# Power_Supply.net
KiCad netlist of a schematic drawn in Altium Designer
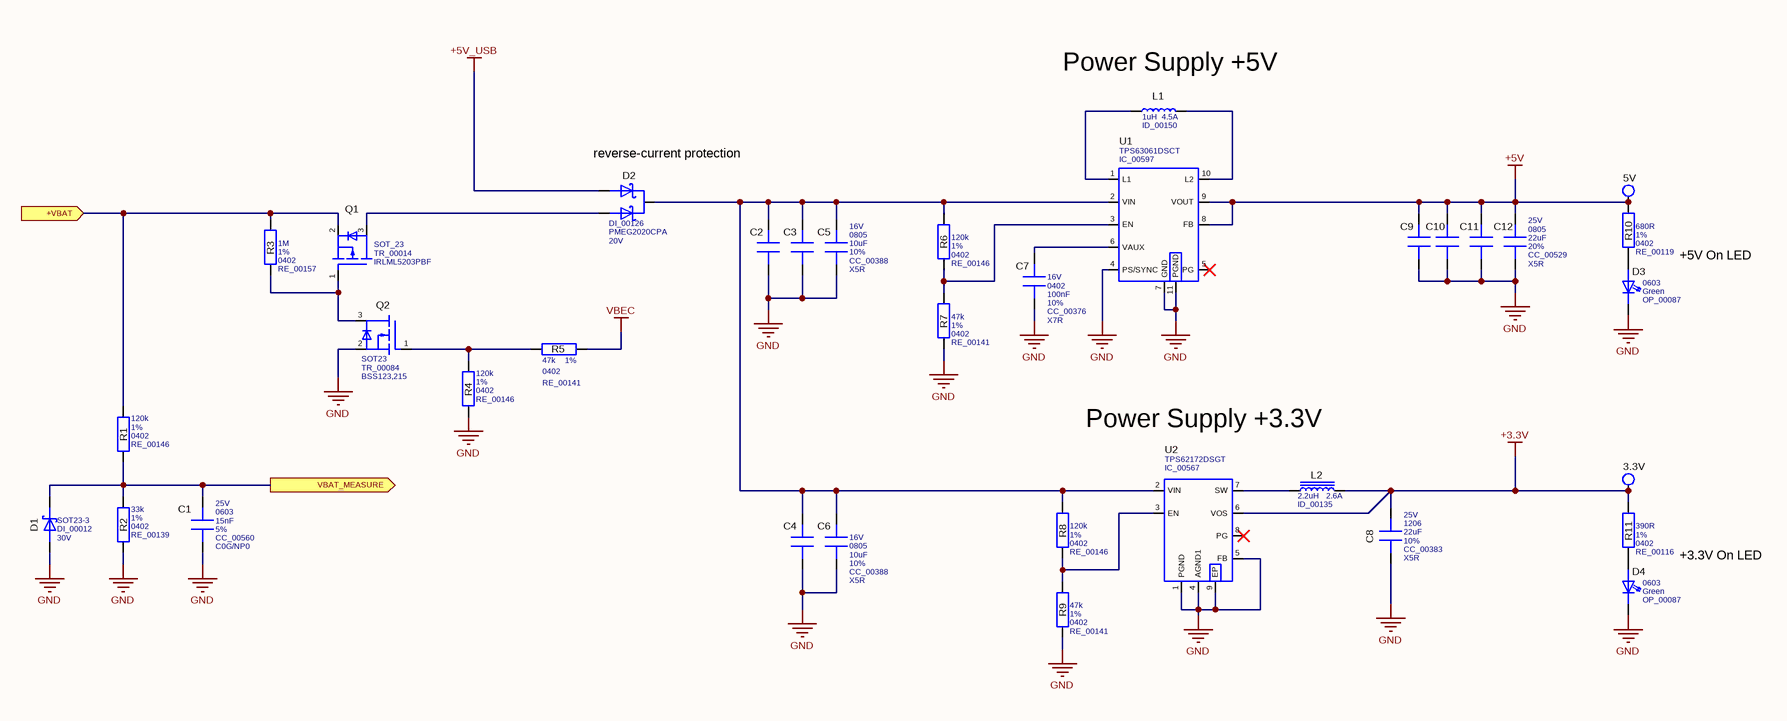
[diagram p0: Power Supply.SchDoc]

(export (version "E")
  (design (tool "Eeschema 10.0.6"))
  (components
    (comp (ref "3.3V")
      (value "testpoint")
      (footprint "CO_00057N")
      (description "Testpoint 1.6mm Bohrung 1mm")
      (fields
        (field (name "PART_NUMBER") "CO_00057")
        (field (name "POWER") "0W")
        (field (name "CREATOR") "Sirnik Heimo")
      )
      (libsource (lib "Central Library") (part "testpoint"))
    )
    (comp (ref "5V")
      (value "testpoint")
      (footprint "CO_00057N")
      (description "Testpoint 1.6mm Bohrung 1mm")
      (fields
        (field (name "PART_NUMBER") "CO_00057")
        (field (name "POWER") "0W")
        (field (name "CREATOR") "Sirnik Heimo")
      )
      (libsource (lib "Central Library") (part "testpoint"))
    )
    (comp (ref "C1")
      (value "capacitor")
      (footprint "CS1600X800X900X350X1250L")
      (fields
        (field (name "VOLTAGE") "25V")
        (field (name "PACKAGE") "0603")
        (field (name "CAPACITANCE") "15nF")
        (field (name "TOLERANCE") "5%")
        (field (name "PART_NUMBER") "CC_00560")
        (field (name "DIELECTRIC_MATERIAL") "C0G/NP0")
        (field (name "CREATOR") "Krenn Markus")
      )
      (libsource (lib "Central Library") (part "capacitor"))
    )
    (comp (ref "C2")
      (value "capacitor")
      (footprint "CS2000x1250x1250x350x1650L")
      (fields
        (field (name "VOLTAGE") "16V")
        (field (name "TOLERANCE") "10%")
        (field (name "PART_NUMBER") "CC_00388")
        (field (name "CREATOR") "Krenn Markus")
      )
      (libsource (lib "Central Library") (part "capacitor"))
    )
    (comp (ref "C3")
      (value "capacitor")
      (footprint "CS2000x1250x1250x350x1650L")
      (fields
        (field (name "VOLTAGE") "16V")
        (field (name "TOLERANCE") "10%")
        (field (name "PART_NUMBER") "CC_00388")
        (field (name "CREATOR") "Krenn Markus")
      )
      (libsource (lib "Central Library") (part "capacitor"))
    )
    (comp (ref "C4")
      (value "capacitor")
      (footprint "CS2000x1250x1250x350x1650L")
      (fields
        (field (name "VOLTAGE") "16V")
        (field (name "TOLERANCE") "10%")
        (field (name "PART_NUMBER") "CC_00388")
        (field (name "CREATOR") "Krenn Markus")
      )
      (libsource (lib "Central Library") (part "capacitor"))
    )
    (comp (ref "C5")
      (value "capacitor")
      (footprint "CS2000x1250x1250x350x1650L")
      (fields
        (field (name "VOLTAGE") "16V")
        (field (name "PACKAGE") "0805")
        (field (name "CAPACITANCE") "10uF")
        (field (name "TOLERANCE") "10%")
        (field (name "PART_NUMBER") "CC_00388")
        (field (name "DIELECTRIC_MATERIAL") "X5R")
        (field (name "CREATOR") "Krenn Markus")
      )
      (libsource (lib "Central Library") (part "capacitor"))
    )
    (comp (ref "C6")
      (value "capacitor")
      (footprint "CS2000x1250x1250x350x1650L")
      (fields
        (field (name "VOLTAGE") "16V")
        (field (name "PACKAGE") "0805")
        (field (name "CAPACITANCE") "10uF")
        (field (name "TOLERANCE") "10%")
        (field (name "PART_NUMBER") "CC_00388")
        (field (name "DIELECTRIC_MATERIAL") "X5R")
        (field (name "CREATOR") "Krenn Markus")
      )
      (libsource (lib "Central Library") (part "capacitor"))
    )
    (comp (ref "C7")
      (value "capacitor")
      (footprint "CS1000X500X560X250X820L")
      (fields
        (field (name "VOLTAGE") "16V")
        (field (name "PACKAGE") "0402")
        (field (name "CAPACITANCE") "100nF")
        (field (name "TOLERANCE") "10%")
        (field (name "PART_NUMBER") "CC_00376")
        (field (name "DIELECTRIC_MATERIAL") "X7R")
        (field (name "CREATOR") "Okorn Robert")
      )
      (libsource (lib "Central Library") (part "capacitor"))
    )
    (comp (ref "C8")
      (value "capacitor")
      (footprint "CS3200x1600x900x500x2700L")
      (fields
        (field (name "VOLTAGE") "25V")
        (field (name "PACKAGE") "1206")
        (field (name "CAPACITANCE") "22uF")
        (field (name "TOLERANCE") "10%")
        (field (name "PART_NUMBER") "CC_00383")
        (field (name "DIELECTRIC_MATERIAL") "X5R")
        (field (name "CREATOR") "Neissl Gernot")
      )
      (libsource (lib "Central Library") (part "capacitor"))
    )
    (comp (ref "C9")
      (value "capacitor")
      (footprint "CS2000x1250x1250x350x1650L")
      (fields
        (field (name "VOLTAGE") "25V")
        (field (name "TOLERANCE") "20%")
        (field (name "PART_NUMBER") "CC_00529")
        (field (name "CREATOR") "Neissl Gernot")
      )
      (libsource (lib "Central Library") (part "capacitor"))
    )
    (comp (ref "C10")
      (value "capacitor")
      (footprint "CS2000x1250x1250x350x1650L")
      (fields
        (field (name "VOLTAGE") "25V")
        (field (name "TOLERANCE") "20%")
        (field (name "PART_NUMBER") "CC_00529")
        (field (name "CREATOR") "Neissl Gernot")
      )
      (libsource (lib "Central Library") (part "capacitor"))
    )
    (comp (ref "C11")
      (value "capacitor")
      (footprint "CS2000x1250x1250x350x1650L")
      (fields
        (field (name "VOLTAGE") "25V")
        (field (name "TOLERANCE") "20%")
        (field (name "PART_NUMBER") "CC_00529")
        (field (name "CREATOR") "Neissl Gernot")
      )
      (libsource (lib "Central Library") (part "capacitor"))
    )
    (comp (ref "C12")
      (value "capacitor")
      (footprint "CS2000x1250x1250x350x1650L")
      (fields
        (field (name "VOLTAGE") "25V")
        (field (name "PACKAGE") "0805")
        (field (name "CAPACITANCE") "22uF")
        (field (name "TOLERANCE") "20%")
        (field (name "PART_NUMBER") "CC_00529")
        (field (name "DIELECTRIC_MATERIAL") "X5R")
        (field (name "CREATOR") "Neissl Gernot")
      )
      (libsource (lib "Central Library") (part "capacitor"))
    )
    (comp (ref "D1")
      (value "DI_00012")
      (footprint "DI_00012N")
      (description "BAR43 - Schottky Diode, 30V, 100mA")
      (fields
        (field (name "PACKAGE") "SOT23-3")
        (field (name "POWER") "0W")
        (field (name "PART_NUMBER") "DI_00012")
        (field (name "REVERSE_VOLTAGE") "30V")
        (field (name "CREATOR") "Krenn Markus")
      )
      (libsource (lib "Central Library") (part "DI_00012"))
    )
    (comp (ref "D2")
      (value "DI_00126")
      (footprint "DI_00126N")
      (description "2 A low V F  dual MEGA Schottky barrier rectifier")
      (fields
        (field (name "POWER") "500mW")
        (field (name "PART_NUMBER") "DI_00126")
        (field (name "MANUFACTURER_NUMBER") "PMEG2020CPA")
        (field (name "REVERSE_VOLTAGE") "20V")
        (field (name "CREATOR") "Krenn Markus")
      )
      (libsource (lib "Central Library") (part "DI_00126"))
    )
    (comp (ref "D3")
      (value "LED")
      (footprint "OP_00087L")
      (fields
        (field (name "PACKAGE") "0603")
        (field (name "COLOR") "Green")
        (field (name "PART_NUMBER") "OP_00087")
        (field (name "CREATOR") "Krenn Markus")
      )
      (libsource (lib "Central Library") (part "LED"))
    )
    (comp (ref "D4")
      (value "LED")
      (footprint "OP_00087L")
      (fields
        (field (name "PACKAGE") "0603")
        (field (name "COLOR") "Green")
        (field (name "PART_NUMBER") "OP_00087")
        (field (name "CREATOR") "Krenn Markus")
      )
      (libsource (lib "Central Library") (part "LED"))
    )
    (comp (ref "L1")
      (value "inductor")
      (footprint "ID_00150N")
      (fields
        (field (name "INDUCTANCE") "1uH")
        (field (name "PART_NUMBER") "ID_00150")
        (field (name "CURRENT_DC") "4.5A")
        (field (name "CREATOR") "Krenn Markus")
      )
      (libsource (lib "Central Library") (part "inductor"))
    )
    (comp (ref "L2")
      (value "inductor_shielded")
      (footprint "ID_00135N")
      (fields
        (field (name "INDUCTANCE") "2.2uH")
        (field (name "PART_NUMBER") "ID_00135")
        (field (name "CURRENT_DC") "2.6A")
        (field (name "CREATOR") "Krenn Markus")
      )
      (libsource (lib "Central Library") (part "inductor_shielded"))
    )
    (comp (ref "Q1")
      (value "pmosfet")
      (footprint "TR_00014N")
      (fields
        (field (name "PACKAGE") "SOT_23")
        (field (name "PART_NUMBER") "TR_00014")
        (field (name "MANUFACTURER_NUMBER") "IRLML5203PBF")
        (field (name "CREATOR") "Neissl Gernot")
      )
      (libsource (lib "Central Library") (part "pmosfet"))
    )
    (comp (ref "Q2")
      (value "nmosfet")
      (footprint "TR_00084N")
      (fields
        (field (name "PACKAGE") "SOT23")
        (field (name "PART_NUMBER") "TR_00084")
        (field (name "MANUFACTURER_NUMBER") "BSS123,215")
        (field (name "CREATOR") "Weis Gerald")
      )
      (libsource (lib "Central Library") (part "nmosfet"))
    )
    (comp (ref "R1")
      (value "Resistor")
      (footprint "RS1000X500X560X250X820L")
      (fields
        (field (name "RESISTANCE") "120k")
        (field (name "TOLERANCE") "1%")
        (field (name "PACKAGE") "0402")
        (field (name "PART_NUMBER") "RE_00146")
        (field (name "CREATOR") "Krenn Markus")
      )
      (libsource (lib "Central Library") (part "Resistor"))
    )
    (comp (ref "R2")
      (value "Resistor")
      (footprint "RS1000X500X560X250X820L")
      (fields
        (field (name "RESISTANCE") "33k")
        (field (name "TOLERANCE") "1%")
        (field (name "PACKAGE") "0402")
        (field (name "PART_NUMBER") "RE_00139")
        (field (name "CREATOR") "Krenn Markus")
      )
      (libsource (lib "Central Library") (part "Resistor"))
    )
    (comp (ref "R3")
      (value "Resistor")
      (footprint "RS1000X500X560X250X820L")
      (fields
        (field (name "RESISTANCE") "1M")
        (field (name "TOLERANCE") "1%")
        (field (name "PACKAGE") "0402")
        (field (name "PART_NUMBER") "RE_00157")
        (field (name "CREATOR") "Krenn Markus")
      )
      (libsource (lib "Central Library") (part "Resistor"))
    )
    (comp (ref "R4")
      (value "Resistor")
      (footprint "RS1000X500X560X250X820L")
      (fields
        (field (name "RESISTANCE") "120k")
        (field (name "TOLERANCE") "1%")
        (field (name "PACKAGE") "0402")
        (field (name "PART_NUMBER") "RE_00146")
        (field (name "CREATOR") "Krenn Markus")
      )
      (libsource (lib "Central Library") (part "Resistor"))
    )
    (comp (ref "R5")
      (value "Resistor")
      (footprint "RS1000X500X560X250X820L")
      (fields
        (field (name "RESISTANCE") "47k")
        (field (name "TOLERANCE") "1%")
        (field (name "PACKAGE") "0402")
        (field (name "PART_NUMBER") "RE_00141")
        (field (name "CREATOR") "Krenn Markus")
      )
      (libsource (lib "Central Library") (part "Resistor"))
    )
    (comp (ref "R6")
      (value "Resistor")
      (footprint "RS1000X500X560X250X820L")
      (fields
        (field (name "RESISTANCE") "120k")
        (field (name "TOLERANCE") "1%")
        (field (name "PACKAGE") "0402")
        (field (name "PART_NUMBER") "RE_00146")
        (field (name "CREATOR") "Krenn Markus")
      )
      (libsource (lib "Central Library") (part "Resistor"))
    )
    (comp (ref "R7")
      (value "Resistor")
      (footprint "RS1000X500X560X250X820L")
      (fields
        (field (name "RESISTANCE") "47k")
        (field (name "TOLERANCE") "1%")
        (field (name "PACKAGE") "0402")
        (field (name "PART_NUMBER") "RE_00141")
        (field (name "CREATOR") "Krenn Markus")
      )
      (libsource (lib "Central Library") (part "Resistor"))
    )
    (comp (ref "R8")
      (value "Resistor")
      (footprint "RS1000X500X560X250X820L")
      (fields
        (field (name "RESISTANCE") "120k")
        (field (name "TOLERANCE") "1%")
        (field (name "PACKAGE") "0402")
        (field (name "PART_NUMBER") "RE_00146")
        (field (name "CREATOR") "Krenn Markus")
      )
      (libsource (lib "Central Library") (part "Resistor"))
    )
    (comp (ref "R9")
      (value "Resistor")
      (footprint "RS1000X500X560X250X820L")
      (fields
        (field (name "RESISTANCE") "47k")
        (field (name "TOLERANCE") "1%")
        (field (name "PACKAGE") "0402")
        (field (name "PART_NUMBER") "RE_00141")
        (field (name "CREATOR") "Krenn Markus")
      )
      (libsource (lib "Central Library") (part "Resistor"))
    )
    (comp (ref "R10")
      (value "Resistor")
      (footprint "RS1000X500X560X250X820L")
      (fields
        (field (name "RESISTANCE") "680R")
        (field (name "TOLERANCE") "1%")
        (field (name "PACKAGE") "0402")
        (field (name "PART_NUMBER") "RE_00119")
        (field (name "CREATOR") "Krenn Markus")
      )
      (libsource (lib "Central Library") (part "Resistor"))
    )
    (comp (ref "R11")
      (value "Resistor")
      (footprint "RS1000X500X560X250X820L")
      (fields
        (field (name "RESISTANCE") "390R")
        (field (name "TOLERANCE") "1%")
        (field (name "PACKAGE") "0402")
        (field (name "PART_NUMBER") "RE_00116")
        (field (name "CREATOR") "Krenn Markus")
      )
      (libsource (lib "Central Library") (part "Resistor"))
    )
    (comp (ref "U1")
      (value "IC_00597")
      (footprint "IC_00597N")
      (description "TPS62172DSGT - Step-Down Converter with DCS-Control")
      (fields
        (field (name "PART_NUMBER") "IC_00597")
        (field (name "MANUFACTURER_NUMBER") "TPS63061DSCT")
        (field (name "CREATOR") "Krenn Markus")
      )
      (libsource (lib "Central Library") (part "IC_00597"))
    )
    (comp (ref "U2")
      (value "IC_00567")
      (footprint "IC_00567N")
      (description "TPS62172DSGT - Step-Down Converter with DCS-Control")
      (fields
        (field (name "PART_NUMBER") "IC_00567")
        (field (name "MANUFACTURER_NUMBER") "TPS62172DSGT")
        (field (name "CREATOR") "Krenn Markus")
      )
      (libsource (lib "Central Library") (part "IC_00567"))
    )
  )
  (nets
    (net (code "1") (name "+3.3V") (class "Default")
      (node (ref "3.3V") (pin "1") (pinfunction "PIN1_1") (pintype "passive"))
      (node (ref "C8") (pin "2") (pinfunction "PIN2_2") (pintype "passive"))
      (node (ref "L2") (pin "2") (pinfunction "PIN2_2") (pintype "passive"))
      (node (ref "R11") (pin "2") (pinfunction "PIN2_2") (pintype "passive"))
      (node (ref "U2") (pin "6") (pinfunction "VOS_6") (pintype "passive"))
    )
    (net (code "2") (name "+5V") (class "Default")
      (node (ref "5V") (pin "1") (pinfunction "PIN1_1") (pintype "passive"))
      (node (ref "C10") (pin "2") (pinfunction "PIN2_2") (pintype "passive"))
      (node (ref "C11") (pin "2") (pinfunction "PIN2_2") (pintype "passive"))
      (node (ref "C12") (pin "2") (pinfunction "PIN2_2") (pintype "passive"))
      (node (ref "C9") (pin "2") (pinfunction "PIN2_2") (pintype "passive"))
      (node (ref "R10") (pin "2") (pinfunction "PIN2_2") (pintype "passive"))
      (node (ref "U1") (pin "8") (pinfunction "FB_8") (pintype "passive"))
      (node (ref "U1") (pin "9") (pinfunction "VOUT_9") (pintype "passive"))
    )
    (net (code "3") (name "+5V_USB") (class "Default")
      (node (ref "D2") (pin "2") (pinfunction "A1_2") (pintype "passive"))
    )
    (net (code "4") (name "/+VBAT") (class "Default")
      (node (ref "Q1") (pin "2") (pinfunction "S_2") (pintype "passive"))
      (node (ref "R1") (pin "2") (pinfunction "PIN2_2") (pintype "passive"))
      (node (ref "R3") (pin "2") (pinfunction "PIN2_2") (pintype "passive"))
    )
    (net (code "5") (name "/VBAT_MEASURE") (class "Default")
      (node (ref "C1") (pin "2") (pinfunction "PIN2_2") (pintype "passive"))
      (node (ref "D1") (pin "3") (pinfunction "CATHODE_3") (pintype "passive"))
      (node (ref "R1") (pin "1") (pinfunction "PIN1_1") (pintype "passive"))
      (node (ref "R2") (pin "2") (pinfunction "PIN2_2") (pintype "passive"))
    )
    (net (code "6") (name "GND") (class "Default")
      (node (ref "C1") (pin "1") (pinfunction "PIN1_1") (pintype "passive"))
      (node (ref "C10") (pin "1") (pinfunction "PIN1_1") (pintype "passive"))
      (node (ref "C11") (pin "1") (pinfunction "PIN1_1") (pintype "passive"))
      (node (ref "C12") (pin "1") (pinfunction "PIN1_1") (pintype "passive"))
      (node (ref "C2") (pin "1") (pinfunction "PIN1_1") (pintype "passive"))
      (node (ref "C3") (pin "1") (pinfunction "PIN1_1") (pintype "passive"))
      (node (ref "C4") (pin "1") (pinfunction "PIN1_1") (pintype "passive"))
      (node (ref "C5") (pin "1") (pinfunction "PIN1_1") (pintype "passive"))
      (node (ref "C6") (pin "1") (pinfunction "PIN1_1") (pintype "passive"))
      (node (ref "C7") (pin "1") (pinfunction "PIN1_1") (pintype "passive"))
      (node (ref "C8") (pin "1") (pinfunction "PIN1_1") (pintype "passive"))
      (node (ref "C9") (pin "1") (pinfunction "PIN1_1") (pintype "passive"))
      (node (ref "D1") (pin "1") (pinfunction "ANODE_1") (pintype "passive"))
      (node (ref "D3") (pin "1") (pinfunction "CATHODE_1") (pintype "passive"))
      (node (ref "D4") (pin "1") (pinfunction "CATHODE_1") (pintype "passive"))
      (node (ref "Q2") (pin "2") (pinfunction "S_2") (pintype "passive"))
      (node (ref "R2") (pin "1") (pinfunction "PIN1_1") (pintype "passive"))
      (node (ref "R4") (pin "1") (pinfunction "PIN1_1") (pintype "passive"))
      (node (ref "R7") (pin "2") (pinfunction "PIN2_2") (pintype "passive"))
      (node (ref "R9") (pin "2") (pinfunction "PIN2_2") (pintype "passive"))
      (node (ref "U1") (pin "11") (pinfunction "PGND_11") (pintype "passive"))
      (node (ref "U1") (pin "4") (pinfunction "PS/SYNC_4") (pintype "passive"))
      (node (ref "U1") (pin "7") (pinfunction "GND_7") (pintype "passive"))
      (node (ref "U2") (pin "1") (pinfunction "PGND_1") (pintype "passive"))
      (node (ref "U2") (pin "4") (pinfunction "AGND1_4") (pintype "passive"))
      (node (ref "U2") (pin "5") (pinfunction "FB_5") (pintype "passive"))
      (node (ref "U2") (pin "9") (pinfunction "EP_9") (pintype "passive"))
    )
    (net (code "7") (name "Net-(C2-PIN2)") (class "Default")
      (node (ref "C2") (pin "2") (pinfunction "PIN2_2") (pintype "passive"))
      (node (ref "C3") (pin "2") (pinfunction "PIN2_2") (pintype "passive"))
      (node (ref "C4") (pin "2") (pinfunction "PIN2_2") (pintype "passive"))
      (node (ref "C5") (pin "2") (pinfunction "PIN2_2") (pintype "passive"))
      (node (ref "C6") (pin "2") (pinfunction "PIN2_2") (pintype "passive"))
      (node (ref "D2") (pin "3") (pinfunction "C_3") (pintype "passive"))
      (node (ref "R6") (pin "2") (pinfunction "PIN2_2") (pintype "passive"))
      (node (ref "R8") (pin "2") (pinfunction "PIN2_2") (pintype "passive"))
      (node (ref "U1") (pin "2") (pinfunction "VIN_2") (pintype "passive"))
      (node (ref "U2") (pin "2") (pinfunction "VIN_2") (pintype "passive"))
    )
    (net (code "8") (name "Net-(C7-PIN2)") (class "Default")
      (node (ref "C7") (pin "2") (pinfunction "PIN2_2") (pintype "passive"))
      (node (ref "U1") (pin "6") (pinfunction "VAUX_6") (pintype "passive"))
    )
    (net (code "9") (name "Net-(D2-A)") (class "Default")
      (node (ref "D2") (pin "1") (pinfunction "A_1") (pintype "passive"))
      (node (ref "Q1") (pin "3") (pinfunction "D_3") (pintype "passive"))
    )
    (net (code "10") (name "Net-(D3-ANODE)") (class "Default")
      (node (ref "D3") (pin "2") (pinfunction "ANODE_2") (pintype "passive"))
      (node (ref "R10") (pin "1") (pinfunction "PIN1_1") (pintype "passive"))
    )
    (net (code "11") (name "Net-(D4-ANODE)") (class "Default")
      (node (ref "D4") (pin "2") (pinfunction "ANODE_2") (pintype "passive"))
      (node (ref "R11") (pin "1") (pinfunction "PIN1_1") (pintype "passive"))
    )
    (net (code "12") (name "Net-(L1-PIN1)") (class "Default")
      (node (ref "L1") (pin "1") (pinfunction "PIN1_1") (pintype "passive"))
      (node (ref "U1") (pin "1") (pinfunction "L1_1") (pintype "passive"))
    )
    (net (code "13") (name "Net-(L1-PIN2)") (class "Default")
      (node (ref "L1") (pin "2") (pinfunction "PIN2_2") (pintype "passive"))
      (node (ref "U1") (pin "10") (pinfunction "L2_10") (pintype "passive"))
    )
    (net (code "14") (name "Net-(L2-PIN1)") (class "Default")
      (node (ref "L2") (pin "1") (pinfunction "PIN1_1") (pintype "passive"))
      (node (ref "U2") (pin "7") (pinfunction "SW_7") (pintype "passive"))
    )
    (net (code "15") (name "Net-(Q1-G)") (class "Default")
      (node (ref "Q1") (pin "1") (pinfunction "G_1") (pintype "passive"))
      (node (ref "Q2") (pin "3") (pinfunction "D_3") (pintype "passive"))
      (node (ref "R3") (pin "1") (pinfunction "PIN1_1") (pintype "passive"))
    )
    (net (code "16") (name "Net-(Q2-G)") (class "Default")
      (node (ref "Q2") (pin "1") (pinfunction "G_1") (pintype "passive"))
      (node (ref "R4") (pin "2") (pinfunction "PIN2_2") (pintype "passive"))
      (node (ref "R5") (pin "1") (pinfunction "PIN1_1") (pintype "passive"))
    )
    (net (code "17") (name "Net-(R6-PIN1)") (class "Default")
      (node (ref "R6") (pin "1") (pinfunction "PIN1_1") (pintype "passive"))
      (node (ref "R7") (pin "1") (pinfunction "PIN1_1") (pintype "passive"))
      (node (ref "U1") (pin "3") (pinfunction "EN_3") (pintype "passive"))
    )
    (net (code "18") (name "Net-(R8-PIN1)") (class "Default")
      (node (ref "R8") (pin "1") (pinfunction "PIN1_1") (pintype "passive"))
      (node (ref "R9") (pin "1") (pinfunction "PIN1_1") (pintype "passive"))
      (node (ref "U2") (pin "3") (pinfunction "EN_3") (pintype "passive"))
    )
    (net (code "19") (name "VBEC") (class "Default")
      (node (ref "R5") (pin "2") (pinfunction "PIN2_2") (pintype "passive"))
    )
    (net (code "20") (name "unconnected-(U1-PG-Pad5)") (class "Default")
      (node (ref "U1") (pin "5") (pinfunction "PG_5") (pintype "passive+no_connect"))
    )
    (net (code "21") (name "unconnected-(U2-PG-Pad8)") (class "Default")
      (node (ref "U2") (pin "8") (pinfunction "PG_8") (pintype "passive+no_connect"))
    )
  )
)
